# PSU.net
KiCad netlist of a schematic drawn in Altium Designer
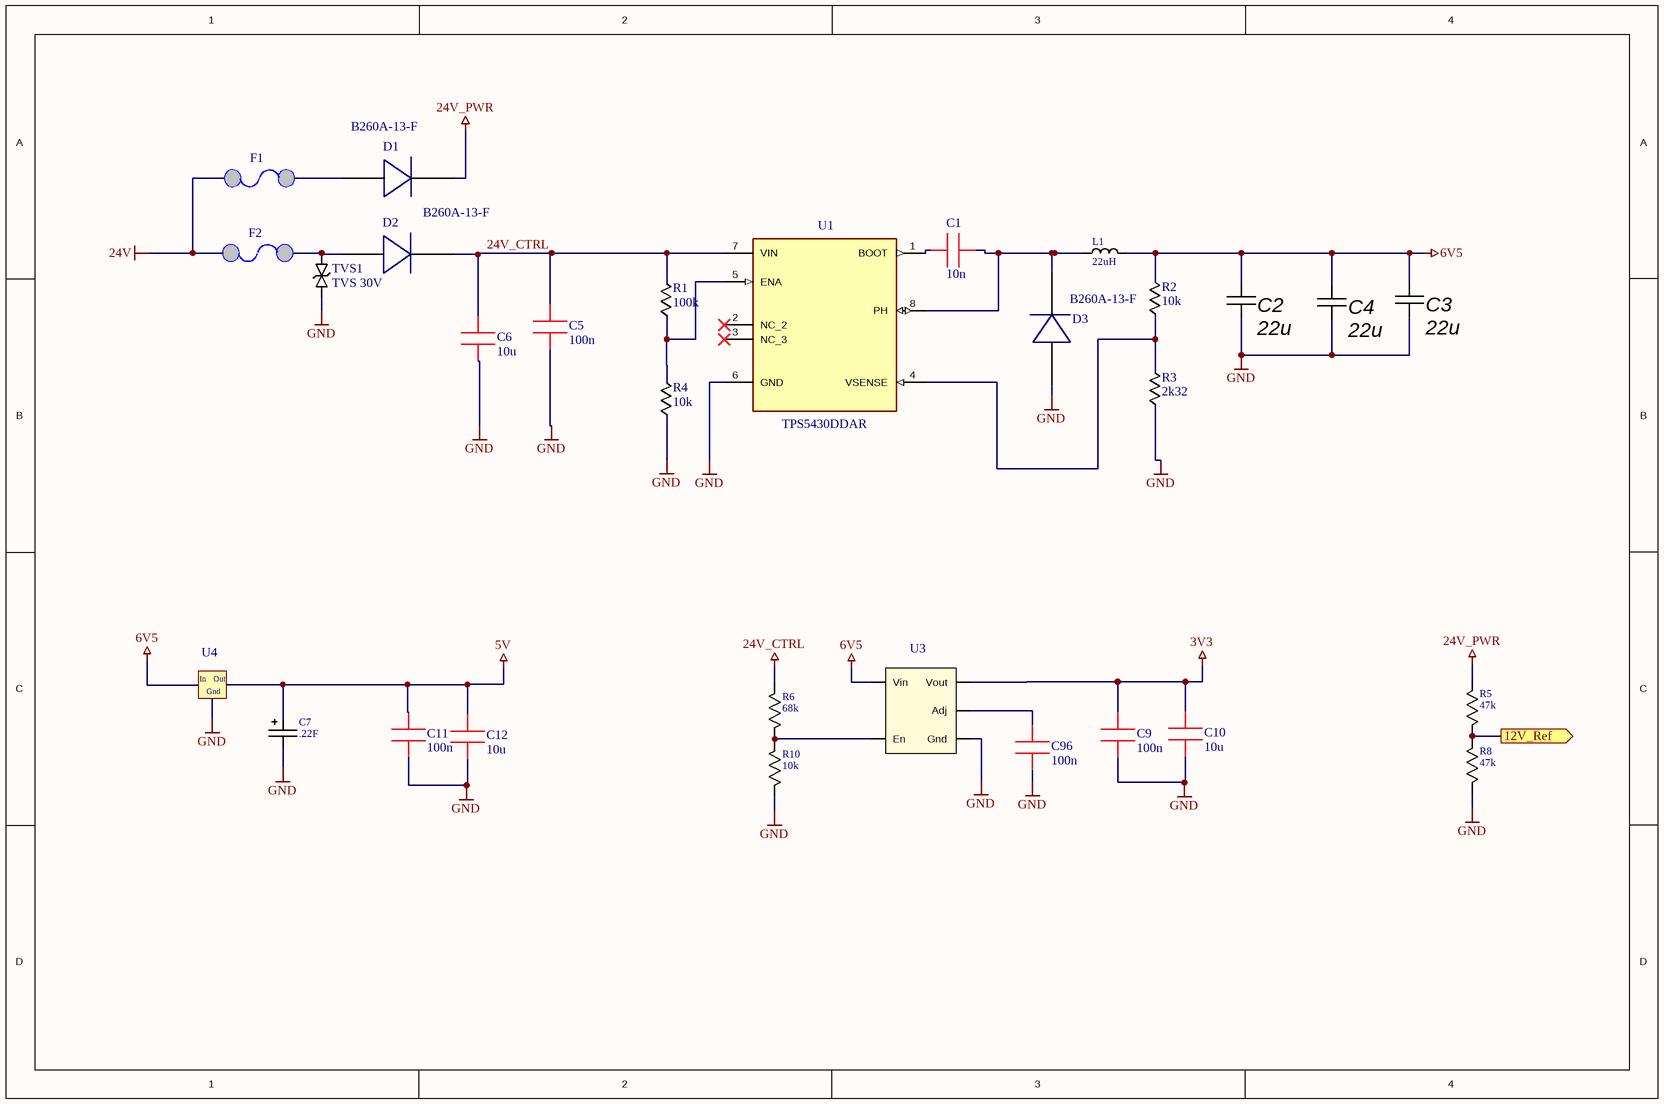
[diagram p0: PSU.SchDoc]

(export (version "E")
  (design (tool "Eeschema 10.0.6"))
  (components
    (comp (ref "C1")
      (value "10n")
      (footprint "0603")
      (description "CC0603JRX7R9BB103")
      (libsource (lib "kontr") (part "0603 CAP"))
    )
    (comp (ref "C2")
      (value "22u")
      (footprint "0805")
      (description "CC0805MKX5R6BB226")
      (fields (field (name "TOLERANCE") "10%"))
      (libsource (lib "kontr") (part "Capacitor"))
    )
    (comp (ref "C3")
      (value "22u")
      (footprint "0805")
      (description "CC0805MKX5R6BB226")
      (fields (field (name "TOLERANCE") "10%"))
      (libsource (lib "kontr") (part "Capacitor"))
    )
    (comp (ref "C4")
      (value "22u")
      (footprint "0805")
      (description "CC0805MKX5R6BB226")
      (fields (field (name "TOLERANCE") "10%"))
      (libsource (lib "kontr") (part "Capacitor"))
    )
    (comp (ref "C5")
      (value "100n")
      (footprint "0603")
      (description "CC0603KRX7R9BB104")
      (libsource (lib "kontr") (part "0603 CAP"))
    )
    (comp (ref "C6")
      (value "10u")
      (footprint "1210")
      (description "GRM32ER71H106KA12L")
      (libsource (lib "kontr") (part "1206 Cap"))
    )
    (comp (ref "C7")
      (value ".22F")
      (footprint "Supercap -D20-V")
      (description "5R5D10F33V")
      (libsource (lib "levin") (part "Capacitor Polar"))
    )
    (comp (ref "C9")
      (value "100n")
      (footprint "0603")
      (description "CC0603KRX7R9BB104")
      (libsource (lib "kontr") (part "0603 CAP"))
    )
    (comp (ref "C10")
      (value "10u")
      (footprint "0603")
      (description "GRM188R61C106MA73D")
      (libsource (lib "kontr") (part "0603 CAP"))
    )
    (comp (ref "C11")
      (value "100n")
      (footprint "0603")
      (description "CC0603KRX7R9BB104")
      (libsource (lib "kontr") (part "0603 CAP"))
    )
    (comp (ref "C12")
      (value "10u")
      (footprint "0603")
      (description "GRM188R61C106MA73D")
      (libsource (lib "kontr") (part "0603 CAP"))
    )
    (comp (ref "C96")
      (value "100n")
      (footprint "0603")
      (description "CC0603KRX7R9BB104")
      (libsource (lib "kontr") (part "0603 CAP"))
    )
    (comp (ref "D1")
      (value "B260A-13-F")
      (footprint "DO-214Pol")
      (libsource (lib "kontr") (part "B260A-13-F"))
    )
    (comp (ref "D2")
      (value "B260A-13-F")
      (footprint "DO-214Pol")
      (libsource (lib "kontr") (part "B260A-13-F"))
    )
    (comp (ref "D3")
      (value "B260A-13-F")
      (footprint "DO-214Pol")
      (libsource (lib "kontr") (part "B260A-13-F"))
    )
    (comp (ref "F1")
      (value "Resettable FUSE")
      (footprint "1812")
      (description "MF-MSMF030-2")
      (libsource (lib "kontr") (part "Fuse PTS"))
    )
    (comp (ref "F2")
      (value "Resettable FUSE")
      (footprint "1812")
      (description "MF-MSMF030-2")
      (libsource (lib "kontr") (part "Fuse PTS"))
    )
    (comp (ref "L1")
      (value "22uH")
      (footprint "CDRH127")
      (description "CDRH127/LDNP-220MC")
      (libsource (lib "levin") (part "Inductor CDRH127"))
    )
    (comp (ref "R1")
      (value "100k")
      (footprint "0603")
      (description "RC0603FR-07100KL")
      (libsource (lib "kontr") (part "0603 RES"))
    )
    (comp (ref "R2")
      (value "10k")
      (footprint "0603")
      (description "RC0603FR-0710KL")
      (libsource (lib "kontr") (part "0603 RES"))
    )
    (comp (ref "R3")
      (value "2k32")
      (footprint "0603")
      (description "RC0603FR-072K32L")
      (libsource (lib "kontr") (part "0603 RES"))
    )
    (comp (ref "R4")
      (value "10k")
      (footprint "0603")
      (description "RC0603FR-0710KL")
      (libsource (lib "kontr") (part "0603 RES"))
    )
    (comp (ref "R5")
      (value "47k")
      (footprint "RES 0603")
      (description "RC0603FR-0747KL")
      (libsource (lib "levin") (part "Resistor"))
    )
    (comp (ref "R6")
      (value "68k")
      (footprint "RES 0603")
      (description "RC0603JR-0768KL")
      (libsource (lib "levin") (part "Resistor"))
    )
    (comp (ref "R8")
      (value "47k")
      (footprint "RES 0603")
      (description "RC0603FR-0747KL")
      (libsource (lib "levin") (part "Resistor"))
    )
    (comp (ref "R10")
      (value "10k")
      (footprint "RES 0603")
      (description "RC0603FR-0710KL")
      (libsource (lib "levin") (part "Resistor"))
    )
    (comp (ref "TVS1")
      (value "TVS 30V")
      (footprint "DO-214AC")
      (description "SMAJ30CA")
      (libsource (lib "kontr") (part "TVS"))
    )
    (comp (ref "U1")
      (value "TPS5430DDAR")
      (footprint "SOIC-8 + Thermal Pad")
      (libsource (lib "levin") (part "TPS5430DDAR"))
    )
    (comp (ref "U3")
      (value "LDO with Enable Pin")
      (footprint "SOT-23-5")
      (description "LM8805SF5-3.3")
      (libsource (lib "levin") (part "LM8805"))
    )
    (comp (ref "U4")
      (value "LDO 5V")
      (footprint "SOT223")
      (description "LD1117S50CTR")
      (libsource (lib "kontr") (part "LDO"))
    )
  )
  (nets
    (net (code "1") (name "/12V_Ref") (class "Default")
      (node (ref "R5") (pin "2") (pinfunction "2_2") (pintype "passive"))
      (node (ref "R8") (pin "1") (pinfunction "1_1") (pintype "passive"))
    )
    (net (code "2") (name "3V3") (class "Default")
      (node (ref "C10") (pin "1") (pinfunction "1_1") (pintype "passive"))
      (node (ref "C9") (pin "1") (pinfunction "1_1") (pintype "passive"))
      (node (ref "U3") (pin "5") (pinfunction "Vout_5") (pintype "passive"))
    )
    (net (code "3") (name "5V") (class "Default")
      (node (ref "C11") (pin "1") (pinfunction "1_1") (pintype "passive"))
      (node (ref "C12") (pin "1") (pinfunction "1_1") (pintype "passive"))
      (node (ref "C7") (pin "2") (pinfunction "2_2") (pintype "passive"))
      (node (ref "U4") (pin "2") (pinfunction "OUT_2") (pintype "passive"))
    )
    (net (code "4") (name "6V5") (class "Default")
      (node (ref "C2") (pin "2") (pinfunction "2_2") (pintype "passive"))
      (node (ref "C3") (pin "2") (pinfunction "2_2") (pintype "passive"))
      (node (ref "C4") (pin "2") (pinfunction "2_2") (pintype "passive"))
      (node (ref "L1") (pin "2") (pinfunction "2_2") (pintype "passive"))
      (node (ref "R2") (pin "2") (pintype "passive"))
      (node (ref "U3") (pin "1") (pinfunction "Vin_1") (pintype "passive"))
      (node (ref "U4") (pin "3") (pinfunction "IN_3") (pintype "passive"))
    )
    (net (code "5") (name "24V") (class "Default")
      (node (ref "F1") (pin "2") (pinfunction "2_2") (pintype "passive"))
      (node (ref "F2") (pin "2") (pinfunction "2_2") (pintype "passive"))
    )
    (net (code "6") (name "24V_CTRL") (class "Default")
      (node (ref "C5") (pin "2") (pinfunction "2_2") (pintype "passive"))
      (node (ref "C6") (pin "1") (pinfunction "1_1") (pintype "passive"))
      (node (ref "D2") (pin "1") (pinfunction "1_1") (pintype "passive"))
      (node (ref "R1") (pin "2") (pintype "passive"))
      (node (ref "R6") (pin "1") (pinfunction "1_1") (pintype "passive"))
      (node (ref "U1") (pin "7") (pinfunction "VIN_7") (pintype "power_in"))
    )
    (net (code "7") (name "24V_PWR") (class "Default")
      (node (ref "D1") (pin "1") (pinfunction "1_1") (pintype "passive"))
      (node (ref "R5") (pin "1") (pinfunction "1_1") (pintype "passive"))
    )
    (net (code "8") (name "GND") (class "Default")
      (node (ref "C10") (pin "2") (pinfunction "2_2") (pintype "passive"))
      (node (ref "C11") (pin "2") (pinfunction "2_2") (pintype "passive"))
      (node (ref "C12") (pin "2") (pinfunction "2_2") (pintype "passive"))
      (node (ref "C2") (pin "1") (pinfunction "1_1") (pintype "passive"))
      (node (ref "C3") (pin "1") (pinfunction "1_1") (pintype "passive"))
      (node (ref "C4") (pin "1") (pinfunction "1_1") (pintype "passive"))
      (node (ref "C5") (pin "1") (pinfunction "1_1") (pintype "passive"))
      (node (ref "C6") (pin "2") (pinfunction "2_2") (pintype "passive"))
      (node (ref "C7") (pin "1") (pinfunction "1_1") (pintype "passive"))
      (node (ref "C9") (pin "2") (pinfunction "2_2") (pintype "passive"))
      (node (ref "C96") (pin "2") (pinfunction "2_2") (pintype "passive"))
      (node (ref "D3") (pin "2") (pinfunction "1_2") (pintype "passive"))
      (node (ref "R10") (pin "2") (pinfunction "2_2") (pintype "passive"))
      (node (ref "R3") (pin "1") (pintype "passive"))
      (node (ref "R4") (pin "1") (pintype "passive"))
      (node (ref "R8") (pin "2") (pinfunction "2_2") (pintype "passive"))
      (node (ref "TVS1") (pin "2") (pinfunction "2_2") (pintype "passive"))
      (node (ref "U1") (pin "6") (pinfunction "GND_6") (pintype "power_in"))
      (node (ref "U3") (pin "2") (pinfunction "Gnd_2") (pintype "passive"))
      (node (ref "U4") (pin "1") (pinfunction "GND_1") (pintype "passive"))
    )
    (net (code "9") (name "Net-(D1-1-Pad2)") (class "Default")
      (node (ref "D1") (pin "2") (pinfunction "1_2") (pintype "passive"))
      (node (ref "F1") (pin "1") (pinfunction "1_1") (pintype "passive"))
    )
    (net (code "10") (name "Net-(D2-1-Pad2)") (class "Default")
      (node (ref "D2") (pin "2") (pinfunction "1_2") (pintype "passive"))
      (node (ref "F2") (pin "1") (pinfunction "1_1") (pintype "passive"))
      (node (ref "TVS1") (pin "1") (pinfunction "1_1") (pintype "passive"))
    )
    (net (code "11") (name "Net-(U1-BOOT)") (class "Default")
      (node (ref "C1") (pin "2") (pinfunction "2_2") (pintype "passive"))
      (node (ref "U1") (pin "1") (pinfunction "BOOT_1") (pintype "output"))
    )
    (net (code "12") (name "Net-(U1-ENA)") (class "Default")
      (node (ref "R1") (pin "1") (pintype "passive"))
      (node (ref "R4") (pin "2") (pintype "passive"))
      (node (ref "U1") (pin "5") (pinfunction "ENA_5") (pintype "input"))
    )
    (net (code "13") (name "Net-(U1-PH)") (class "Default")
      (node (ref "C1") (pin "1") (pinfunction "1_1") (pintype "passive"))
      (node (ref "D3") (pin "1") (pinfunction "1_1") (pintype "passive"))
      (node (ref "L1") (pin "1") (pinfunction "1_1") (pintype "passive"))
      (node (ref "U1") (pin "8") (pinfunction "PH_8") (pintype "bidirectional"))
    )
    (net (code "14") (name "Net-(U1-VSENSE)") (class "Default")
      (node (ref "R2") (pin "1") (pintype "passive"))
      (node (ref "R3") (pin "2") (pintype "passive"))
      (node (ref "U1") (pin "4") (pinfunction "VSENSE_4") (pintype "input"))
    )
    (net (code "15") (name "Net-(U3-Adj)") (class "Default")
      (node (ref "C96") (pin "1") (pinfunction "1_1") (pintype "passive"))
      (node (ref "U3") (pin "4") (pinfunction "Adj_4") (pintype "passive"))
    )
    (net (code "16") (name "Net-(U3-En)") (class "Default")
      (node (ref "R10") (pin "1") (pinfunction "1_1") (pintype "passive"))
      (node (ref "R6") (pin "2") (pinfunction "2_2") (pintype "passive"))
      (node (ref "U3") (pin "3") (pinfunction "En_3") (pintype "passive"))
    )
    (net (code "17") (name "unconnected-(U1-NC_2-Pad2)") (class "Default")
      (node (ref "U1") (pin "2") (pinfunction "NC_2_2") (pintype "passive+no_connect"))
    )
    (net (code "18") (name "unconnected-(U1-NC_3-Pad3)") (class "Default")
      (node (ref "U1") (pin "3") (pinfunction "NC_3_3") (pintype "passive+no_connect"))
    )
  )
)
